# led-er-breakout-single-RJ45.net
KiCad netlist of a schematic drawn in EAGLE
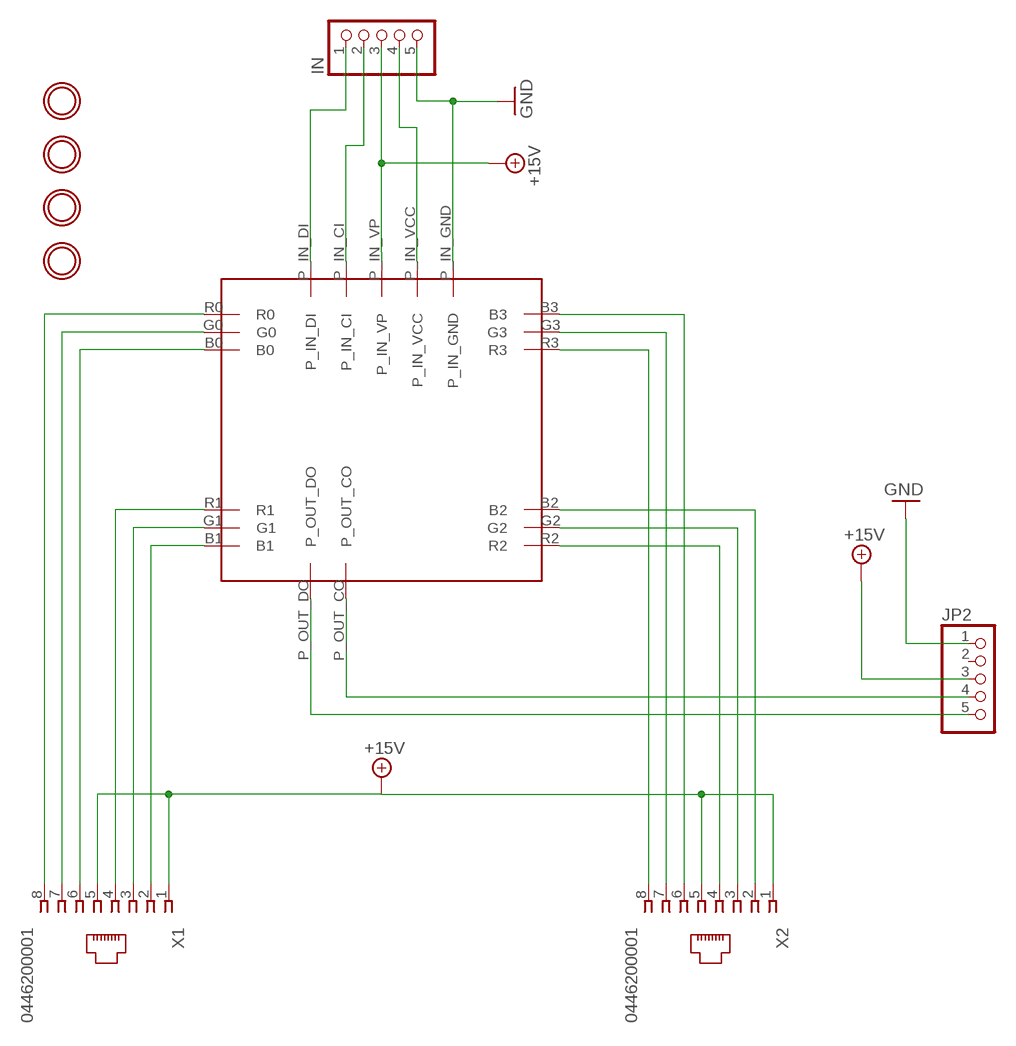
[diagram p0: schematic, sheet 1]

(export (version "E")
  (design (tool "Eeschema 10.0.6"))
  (components
    (comp (ref "IN")
      (value "HEADER-1X5")
      (footprint "eagle-import:1X05_OVAL")
      (libsource (lib "eagle-import") (part "HEADER-1X5"))
    )
    (comp (ref "JP2")
      (value "HEADER-1X5")
      (footprint "eagle-import:1X05_OVAL")
      (libsource (lib "eagle-import") (part "HEADER-1X5"))
    )
    (comp (ref "U$1")
      (value "MOUNTINGHOLE2.0")
      (footprint "eagle-import:MOUNTINGHOLE_2.0_PLATED")
      (libsource (lib "eagle-import") (part "MOUNTINGHOLE2.0"))
    )
    (comp (ref "U$2")
      (value "MOUNTINGHOLE2.0")
      (footprint "eagle-import:MOUNTINGHOLE_2.0_PLATED")
      (libsource (lib "eagle-import") (part "MOUNTINGHOLE2.0"))
    )
    (comp (ref "U$3")
      (value "MOUNTINGHOLE2.0")
      (footprint "eagle-import:MOUNTINGHOLE_2.0_PLATED")
      (libsource (lib "eagle-import") (part "MOUNTINGHOLE2.0"))
    )
    (comp (ref "U$4")
      (value "MOUNTINGHOLE2.0")
      (footprint "eagle-import:MOUNTINGHOLE_2.0_PLATED")
      (libsource (lib "eagle-import") (part "MOUNTINGHOLE2.0"))
    )
    (comp (ref "U$6")
      (value "TLC59711_BREAKOUT")
      (footprint "eagle-import:TLC59711_BREAKOUT")
      (libsource (lib "eagle-import") (part "TLC59711_BREAKOUT"))
    )
    (comp (ref "X1")
      (value "0446200001")
      (footprint "eagle-import:0446200001")
      (libsource (lib "eagle-import") (part "0446200001"))
    )
    (comp (ref "X2")
      (value "0446200001")
      (footprint "eagle-import:0446200001")
      (libsource (lib "eagle-import") (part "0446200001"))
    )
  )
  (nets
    (net (code "1") (name "+15V") (class "Default")
      (node (ref "IN") (pin "3") (pinfunction "3_3") (pintype "passive"))
      (node (ref "JP2") (pin "3") (pinfunction "3_3") (pintype "passive"))
      (node (ref "U$6") (pin "P_IN_VP") (pinfunction "P_IN_VP_P_IN_VP") (pintype "bidirectional"))
      (node (ref "X1") (pin "1") (pinfunction "1_1") (pintype "passive"))
      (node (ref "X1") (pin "5") (pinfunction "5_5") (pintype "passive"))
      (node (ref "X2") (pin "1") (pinfunction "1_1") (pintype "passive"))
      (node (ref "X2") (pin "5") (pinfunction "5_5") (pintype "passive"))
    )
    (net (code "2") (name "GND") (class "Default")
      (node (ref "IN") (pin "5") (pinfunction "5_5") (pintype "passive"))
      (node (ref "JP2") (pin "1") (pinfunction "1_1") (pintype "passive"))
      (node (ref "U$6") (pin "P_IN_GND") (pinfunction "P_IN_GND_P_IN_GND") (pintype "bidirectional"))
    )
    (net (code "3") (name "Net-(IN-Pad1)") (class "Default")
      (node (ref "IN") (pin "1") (pinfunction "1_1") (pintype "passive"))
      (node (ref "U$6") (pin "P_IN_DI") (pinfunction "P_IN_DI_P_IN_DI") (pintype "bidirectional"))
    )
    (net (code "4") (name "Net-(IN-Pad2)") (class "Default")
      (node (ref "IN") (pin "2") (pinfunction "2_2") (pintype "passive"))
      (node (ref "U$6") (pin "P_IN_CI") (pinfunction "P_IN_CI_P_IN_CI") (pintype "bidirectional"))
    )
    (net (code "5") (name "Net-(IN-Pad4)") (class "Default")
      (node (ref "IN") (pin "4") (pinfunction "4_4") (pintype "passive"))
      (node (ref "U$6") (pin "P_IN_VCC") (pinfunction "P_IN_VCC_P_IN_VCC") (pintype "bidirectional"))
    )
    (net (code "6") (name "Net-(JP2-Pad4)") (class "Default")
      (node (ref "JP2") (pin "4") (pinfunction "4_4") (pintype "passive"))
      (node (ref "U$6") (pin "P_OUT_CO") (pinfunction "P_OUT_CO_P_OUT_CO") (pintype "bidirectional"))
    )
    (net (code "7") (name "Net-(JP2-Pad5)") (class "Default")
      (node (ref "JP2") (pin "5") (pinfunction "5_5") (pintype "passive"))
      (node (ref "U$6") (pin "P_OUT_DO") (pinfunction "P_OUT_DO_P_OUT_DO") (pintype "bidirectional"))
    )
    (net (code "8") (name "Net-(U$6-PadB0)") (class "Default")
      (node (ref "U$6") (pin "B0") (pinfunction "B0_B0") (pintype "bidirectional"))
      (node (ref "X1") (pin "6") (pinfunction "6_6") (pintype "passive"))
    )
    (net (code "9") (name "Net-(U$6-PadB1)") (class "Default")
      (node (ref "U$6") (pin "B1") (pinfunction "B1_B1") (pintype "bidirectional"))
      (node (ref "X1") (pin "2") (pinfunction "2_2") (pintype "passive"))
    )
    (net (code "10") (name "Net-(U$6-PadB2)") (class "Default")
      (node (ref "U$6") (pin "B2") (pinfunction "B2_B2") (pintype "bidirectional"))
      (node (ref "X2") (pin "2") (pinfunction "2_2") (pintype "passive"))
    )
    (net (code "11") (name "Net-(U$6-PadB3)") (class "Default")
      (node (ref "U$6") (pin "B3") (pinfunction "B3_B3") (pintype "bidirectional"))
      (node (ref "X2") (pin "6") (pinfunction "6_6") (pintype "passive"))
    )
    (net (code "12") (name "Net-(U$6-PadG0)") (class "Default")
      (node (ref "U$6") (pin "G0") (pinfunction "G0_G0") (pintype "bidirectional"))
      (node (ref "X1") (pin "7") (pinfunction "7_7") (pintype "passive"))
    )
    (net (code "13") (name "Net-(U$6-PadG1)") (class "Default")
      (node (ref "U$6") (pin "G1") (pinfunction "G1_G1") (pintype "bidirectional"))
      (node (ref "X1") (pin "3") (pinfunction "3_3") (pintype "passive"))
    )
    (net (code "14") (name "Net-(U$6-PadG2)") (class "Default")
      (node (ref "U$6") (pin "G2") (pinfunction "G2_G2") (pintype "bidirectional"))
      (node (ref "X2") (pin "3") (pinfunction "3_3") (pintype "passive"))
    )
    (net (code "15") (name "Net-(U$6-PadG3)") (class "Default")
      (node (ref "U$6") (pin "G3") (pinfunction "G3_G3") (pintype "bidirectional"))
      (node (ref "X2") (pin "7") (pinfunction "7_7") (pintype "passive"))
    )
    (net (code "16") (name "Net-(U$6-PadR0)") (class "Default")
      (node (ref "U$6") (pin "R0") (pinfunction "R0_R0") (pintype "bidirectional"))
      (node (ref "X1") (pin "8") (pinfunction "8_8") (pintype "passive"))
    )
    (net (code "17") (name "Net-(U$6-PadR1)") (class "Default")
      (node (ref "U$6") (pin "R1") (pinfunction "R1_R1") (pintype "bidirectional"))
      (node (ref "X1") (pin "4") (pinfunction "4_4") (pintype "passive"))
    )
    (net (code "18") (name "Net-(U$6-PadR2)") (class "Default")
      (node (ref "U$6") (pin "R2") (pinfunction "R2_R2") (pintype "bidirectional"))
      (node (ref "X2") (pin "4") (pinfunction "4_4") (pintype "passive"))
    )
    (net (code "19") (name "Net-(U$6-PadR3)") (class "Default")
      (node (ref "U$6") (pin "R3") (pinfunction "R3_R3") (pintype "bidirectional"))
      (node (ref "X2") (pin "8") (pinfunction "8_8") (pintype "passive"))
    )
    (net (code "20") (name "unconnected-(JP2-Pad2)") (class "Default")
      (node (ref "JP2") (pin "2") (pinfunction "2_2") (pintype "passive"))
    )
  )
)
